# Board_4_Buttons_WS-TASV-3.net
KiCad netlist of a schematic drawn in EAGLE
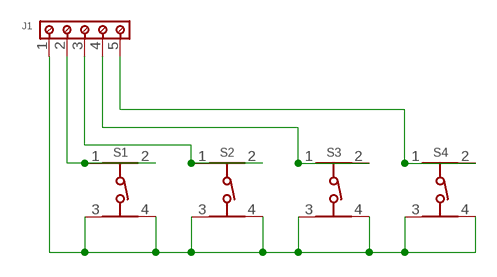
[diagram p0: schematic, sheet 1]

(export (version "E")
  (design (tool "Eeschema 10.0.6"))
  (components
    (comp (ref "J1")
      (value "691709710305")
      (footprint "eagle-import:691709710305")
      (libsource (lib "eagle-import") (part "691709710305"))
    )
    (comp (ref "S1")
      (value "430162073826")
      (footprint "eagle-import:4304X60437X6")
      (libsource (lib "eagle-import") (part "430466043726"))
    )
    (comp (ref "S2")
      (value "430162073826")
      (footprint "eagle-import:4304X60437X6")
      (libsource (lib "eagle-import") (part "430466043726"))
    )
    (comp (ref "S3")
      (value "430162073826")
      (footprint "eagle-import:4304X60437X6")
      (libsource (lib "eagle-import") (part "430466043726"))
    )
    (comp (ref "S4")
      (value "430162073826")
      (footprint "eagle-import:4304X60437X6")
      (libsource (lib "eagle-import") (part "430466043726"))
    )
  )
  (nets
    (net (code "1") (name "Net-(S1-2)") (class "Default")
      (node (ref "J1") (pin "1") (pinfunction "1_1") (pintype "passive"))
      (node (ref "S1") (pin "3") (pinfunction "2_3") (pintype "passive"))
      (node (ref "S1") (pin "4") (pinfunction "4_4") (pintype "passive"))
      (node (ref "S2") (pin "3") (pinfunction "2_3") (pintype "passive"))
      (node (ref "S2") (pin "4") (pinfunction "4_4") (pintype "passive"))
      (node (ref "S3") (pin "3") (pinfunction "2_3") (pintype "passive"))
      (node (ref "S3") (pin "4") (pinfunction "4_4") (pintype "passive"))
      (node (ref "S4") (pin "3") (pinfunction "2_3") (pintype "passive"))
      (node (ref "S4") (pin "4") (pinfunction "4_4") (pintype "passive"))
    )
    (net (code "2") (name "Net-(S1-3)") (class "Default")
      (node (ref "J1") (pin "2") (pinfunction "2_2") (pintype "passive"))
      (node (ref "S1") (pin "1") (pinfunction "1_1") (pintype "passive"))
      (node (ref "S1") (pin "2") (pinfunction "3_2") (pintype "passive"))
    )
    (net (code "3") (name "Net-(S2-3)") (class "Default")
      (node (ref "J1") (pin "3") (pinfunction "3_3") (pintype "passive"))
      (node (ref "S2") (pin "1") (pinfunction "1_1") (pintype "passive"))
      (node (ref "S2") (pin "2") (pinfunction "3_2") (pintype "passive"))
    )
    (net (code "4") (name "Net-(S3-3)") (class "Default")
      (node (ref "J1") (pin "4") (pinfunction "4_4") (pintype "passive"))
      (node (ref "S3") (pin "1") (pinfunction "1_1") (pintype "passive"))
      (node (ref "S3") (pin "2") (pinfunction "3_2") (pintype "passive"))
    )
    (net (code "5") (name "Net-(S4-3)") (class "Default")
      (node (ref "J1") (pin "5") (pinfunction "5_5") (pintype "passive"))
      (node (ref "S4") (pin "1") (pinfunction "1_1") (pintype "passive"))
      (node (ref "S4") (pin "2") (pinfunction "3_2") (pintype "passive"))
    )
  )
)
